# Analog.net
KiCad netlist of a schematic drawn in Altium Designer
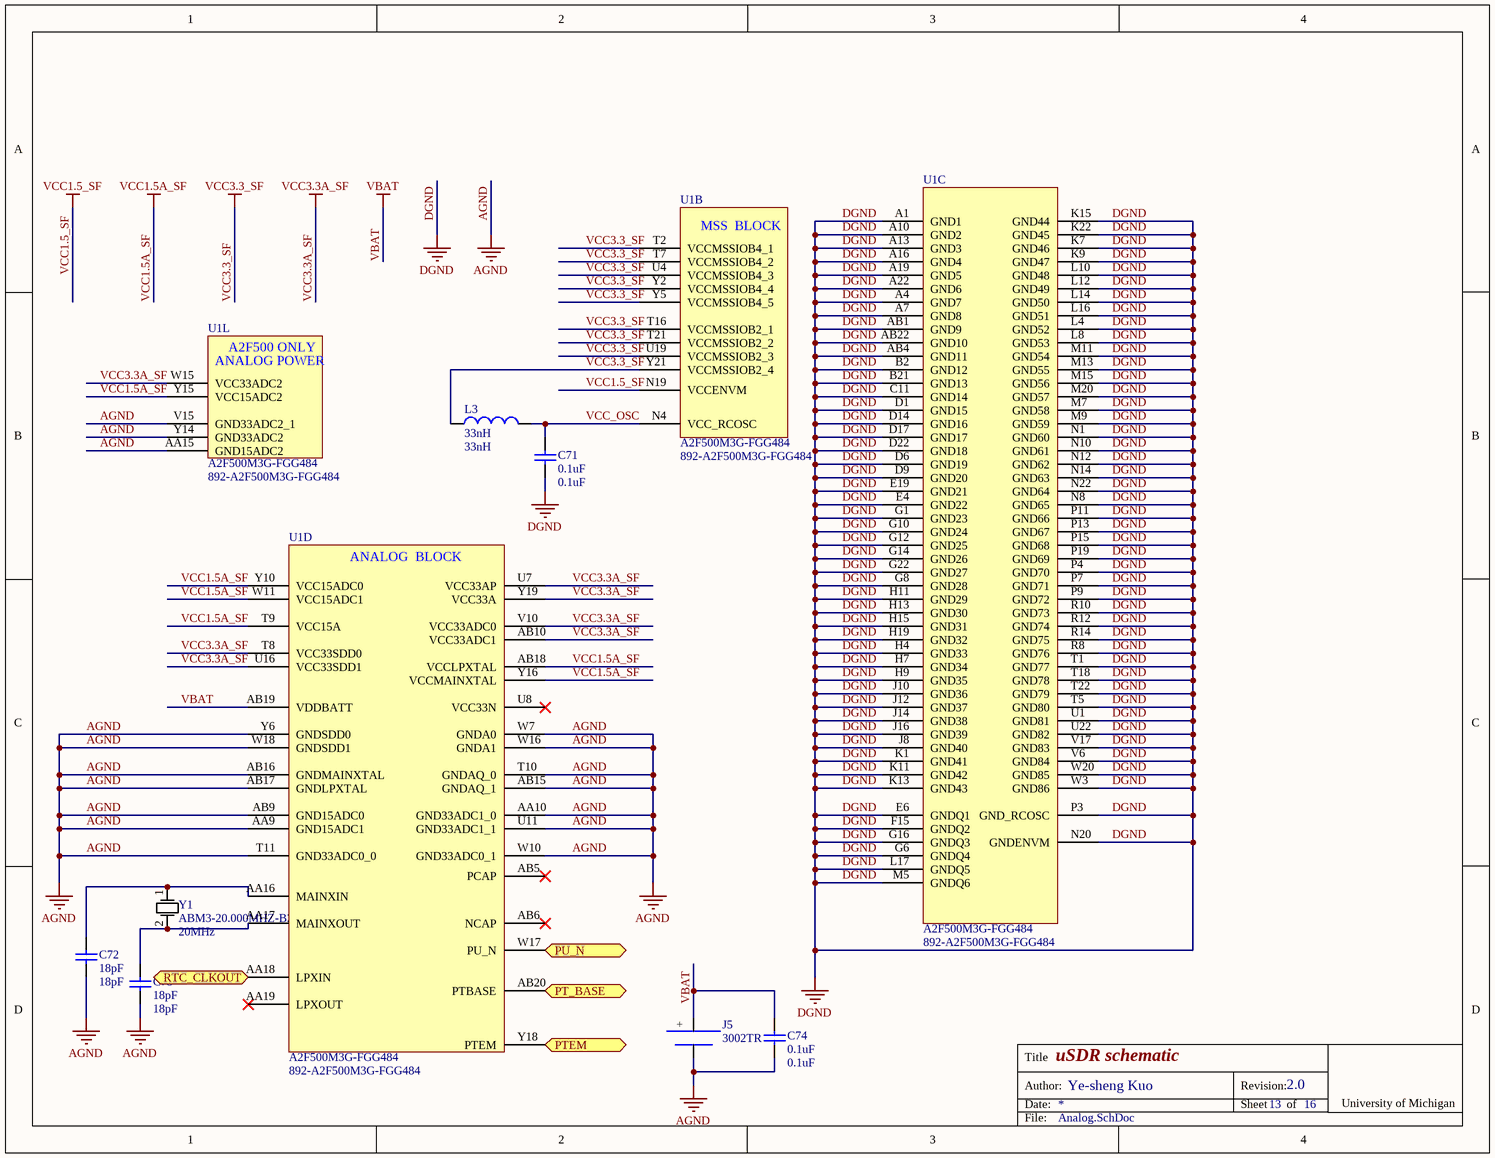
[diagram p0: Analog.SchDoc]

(export (version "E")
  (design (tool "Eeschema 10.0.6"))
  (components
    (comp (ref "C71")
      (value "0.1uF")
      (footprint "0402")
      (description "Capacitor (Semiconductor SIM Model)")
      (fields (field (name "ALTIUM_VALUE") "0.1uF") (field (name "PUBLISHER") "Altium Limited"))
      (libsource (lib "Miscellaneous Devices") (part "Cap Semi"))
    )
    (comp (ref "C72")
      (value "18pF")
      (footprint "0402")
      (description "Capacitor (Semiconductor SIM Model)")
      (fields (field (name "ALTIUM_VALUE") "18pF") (field (name "PUBLISHER") "Altium Limited"))
      (libsource (lib "Miscellaneous Devices") (part "Cap Semi"))
    )
    (comp (ref "C73")
      (value "18pF")
      (footprint "0402")
      (description "Capacitor (Semiconductor SIM Model)")
      (fields (field (name "ALTIUM_VALUE") "18pF") (field (name "PUBLISHER") "Altium Limited"))
      (libsource (lib "Miscellaneous Devices") (part "Cap Semi"))
    )
    (comp (ref "C74")
      (value "0.1uF")
      (footprint "0402")
      (description "Capacitor (Semiconductor SIM Model)")
      (fields (field (name "ALTIUM_VALUE") "0.1uF") (field (name "PUBLISHER") "Altium Limited"))
      (libsource (lib "Miscellaneous Devices") (part "Cap Semi"))
    )
    (comp (ref "J5")
      (value "3002TR")
      (footprint "3002TR")
      (description "HOLDER BATTERY COIN 20MM DIA SMD")
      (libsource (lib "SDR") (part "3002TR"))
    )
    (comp (ref "L3")
      (value "33nH")
      (footprint "0402")
      (description "Inductor")
      (fields (field (name "ALTIUM_VALUE") "33nH") (field (name "PUBLISHER") "Altium Limited"))
      (libsource (lib "Miscellaneous Devices") (part "Inductor"))
    )
    (comp (ref "U1")
      (value "A2F500M3G-FGG484")
      (footprint "BGA100P22X22-484N")
      (description "FPGA - Field Programmable Gate Array 500K System Gates")
      (fields (field (name "SUPPLIER PART NUMBER 1") "892-A2F500M3G-FGG484"))
      (libsource (lib "SDR") (part "F2-200_500-FGG484_1"))
    )
    (comp (ref "Y1")
      (value "ABM3-20.000MHZ-B2-T")
      (footprint "ABM3")
      (description "CRYSTAL 20.000MHZ 18PF SMD")
      (fields (field (name "ALTIUM_VALUE") "20MHz"))
      (libsource (lib "SDR") (part "ABM3"))
    )
  )
  (nets
    (net (code "1") (name "/PTEM") (class "Default")
      (node (ref "U1") (pin "Y18") (pinfunction "PTEM_Y18") (pintype "power_in"))
    )
    (net (code "2") (name "/PT_BASE") (class "Default")
      (node (ref "U1") (pin "AB20") (pinfunction "PTBASE_AB20") (pintype "power_in"))
    )
    (net (code "3") (name "/PU_N") (class "Default")
      (node (ref "U1") (pin "W17") (pinfunction "PU_N_W17") (pintype "power_in"))
    )
    (net (code "4") (name "/RTC_CLKOUT") (class "Default")
      (node (ref "U1") (pin "AA18") (pinfunction "LPXIN_AA18") (pintype "power_in"))
    )
    (net (code "5") (name "/VCC_OSC") (class "Default")
      (node (ref "C71") (pin "2") (pinfunction "2_2") (pintype "passive"))
      (node (ref "L3") (pin "2") (pinfunction "2_2") (pintype "passive"))
      (node (ref "U1") (pin "N4") (pinfunction "VCC_RCOSC_N4") (pintype "power_in"))
    )
    (net (code "6") (name "AGND") (class "Default")
      (node (ref "C72") (pin "1") (pinfunction "1_1") (pintype "passive"))
      (node (ref "C73") (pin "1") (pinfunction "1_1") (pintype "passive"))
      (node (ref "C74") (pin "1") (pinfunction "1_1") (pintype "passive"))
      (node (ref "J5") (pin "neg") (pinfunction "-_neg") (pintype "passive"))
      (node (ref "U1") (pin "AA10") (pinfunction "GND33ADC1_0_AA10") (pintype "power_in"))
      (node (ref "U1") (pin "AA15") (pinfunction "GND15ADC2_AA15") (pintype "power_in"))
      (node (ref "U1") (pin "AA9") (pinfunction "GND15ADC1_AA9") (pintype "power_in"))
      (node (ref "U1") (pin "AB15") (pinfunction "GNDAQ_1_AB15") (pintype "power_in"))
      (node (ref "U1") (pin "AB16") (pinfunction "GNDMAINXTAL_AB16") (pintype "power_in"))
      (node (ref "U1") (pin "AB17") (pinfunction "GNDLPXTAL_AB17") (pintype "power_in"))
      (node (ref "U1") (pin "AB9") (pinfunction "GND15ADC0_AB9") (pintype "power_in"))
      (node (ref "U1") (pin "T10") (pinfunction "GNDAQ_0_T10") (pintype "power_in"))
      (node (ref "U1") (pin "T11") (pinfunction "GND33ADC0_0_T11") (pintype "power_in"))
      (node (ref "U1") (pin "U11") (pinfunction "GND33ADC1_1_U11") (pintype "power_in"))
      (node (ref "U1") (pin "V15") (pinfunction "GND33ADC2_1_V15") (pintype "power_in"))
      (node (ref "U1") (pin "W10") (pinfunction "GND33ADC0_1_W10") (pintype "power_in"))
      (node (ref "U1") (pin "W16") (pinfunction "GNDA1_W16") (pintype "power_in"))
      (node (ref "U1") (pin "W18") (pinfunction "GNDSDD1_W18") (pintype "power_in"))
      (node (ref "U1") (pin "W7") (pinfunction "GNDA0_W7") (pintype "power_in"))
      (node (ref "U1") (pin "Y14") (pinfunction "GND33ADC2_Y14") (pintype "power_in"))
      (node (ref "U1") (pin "Y6") (pinfunction "GNDSDD0_Y6") (pintype "power_in"))
    )
    (net (code "7") (name "DGND") (class "Default")
      (node (ref "C71") (pin "1") (pinfunction "1_1") (pintype "passive"))
      (node (ref "U1") (pin "A1") (pinfunction "GND1_A1") (pintype "power_in"))
      (node (ref "U1") (pin "A10") (pinfunction "GND2_A10") (pintype "power_in"))
      (node (ref "U1") (pin "A13") (pinfunction "GND3_A13") (pintype "power_in"))
      (node (ref "U1") (pin "A16") (pinfunction "GND4_A16") (pintype "power_in"))
      (node (ref "U1") (pin "A19") (pinfunction "GND5_A19") (pintype "power_in"))
      (node (ref "U1") (pin "A22") (pinfunction "GND6_A22") (pintype "power_in"))
      (node (ref "U1") (pin "A4") (pinfunction "GND7_A4") (pintype "power_in"))
      (node (ref "U1") (pin "A7") (pinfunction "GND8_A7") (pintype "power_in"))
      (node (ref "U1") (pin "AB1") (pinfunction "GND9_AB1") (pintype "power_in"))
      (node (ref "U1") (pin "AB22") (pinfunction "GND10_AB22") (pintype "power_in"))
      (node (ref "U1") (pin "AB4") (pinfunction "GND11_AB4") (pintype "power_in"))
      (node (ref "U1") (pin "B2") (pinfunction "GND12_B2") (pintype "power_in"))
      (node (ref "U1") (pin "B21") (pinfunction "GND13_B21") (pintype "power_in"))
      (node (ref "U1") (pin "C11") (pinfunction "GND14_C11") (pintype "power_in"))
      (node (ref "U1") (pin "D1") (pinfunction "GND15_D1") (pintype "power_in"))
      (node (ref "U1") (pin "D14") (pinfunction "GND16_D14") (pintype "power_in"))
      (node (ref "U1") (pin "D17") (pinfunction "GND17_D17") (pintype "power_in"))
      (node (ref "U1") (pin "D22") (pinfunction "GND18_D22") (pintype "power_in"))
      (node (ref "U1") (pin "D6") (pinfunction "GND19_D6") (pintype "power_in"))
      (node (ref "U1") (pin "D9") (pinfunction "GND20_D9") (pintype "power_in"))
      (node (ref "U1") (pin "E19") (pinfunction "GND21_E19") (pintype "power_in"))
      (node (ref "U1") (pin "E4") (pinfunction "GND22_E4") (pintype "power_in"))
      (node (ref "U1") (pin "E6") (pinfunction "GNDQ1_E6") (pintype "power_in"))
      (node (ref "U1") (pin "F15") (pinfunction "GNDQ2_F15") (pintype "power_in"))
      (node (ref "U1") (pin "G1") (pinfunction "GND23_G1") (pintype "power_in"))
      (node (ref "U1") (pin "G10") (pinfunction "GND24_G10") (pintype "power_in"))
      (node (ref "U1") (pin "G12") (pinfunction "GND25_G12") (pintype "power_in"))
      (node (ref "U1") (pin "G14") (pinfunction "GND26_G14") (pintype "power_in"))
      (node (ref "U1") (pin "G16") (pinfunction "GNDQ3_G16") (pintype "power_in"))
      (node (ref "U1") (pin "G22") (pinfunction "GND27_G22") (pintype "power_in"))
      (node (ref "U1") (pin "G6") (pinfunction "GNDQ4_G6") (pintype "power_in"))
      (node (ref "U1") (pin "G8") (pinfunction "GND28_G8") (pintype "power_in"))
      (node (ref "U1") (pin "H11") (pinfunction "GND29_H11") (pintype "power_in"))
      (node (ref "U1") (pin "H13") (pinfunction "GND30_H13") (pintype "power_in"))
      (node (ref "U1") (pin "H15") (pinfunction "GND31_H15") (pintype "power_in"))
      (node (ref "U1") (pin "H19") (pinfunction "GND32_H19") (pintype "power_in"))
      (node (ref "U1") (pin "H4") (pinfunction "GND33_H4") (pintype "power_in"))
      (node (ref "U1") (pin "H7") (pinfunction "GND34_H7") (pintype "power_in"))
      (node (ref "U1") (pin "H9") (pinfunction "GND35_H9") (pintype "power_in"))
      (node (ref "U1") (pin "J10") (pinfunction "GND36_J10") (pintype "power_in"))
      (node (ref "U1") (pin "J12") (pinfunction "GND37_J12") (pintype "power_in"))
      (node (ref "U1") (pin "J14") (pinfunction "GND38_J14") (pintype "power_in"))
      (node (ref "U1") (pin "J16") (pinfunction "GND39_J16") (pintype "power_in"))
      (node (ref "U1") (pin "J8") (pinfunction "GND40_J8") (pintype "power_in"))
      (node (ref "U1") (pin "K1") (pinfunction "GND41_K1") (pintype "power_in"))
      (node (ref "U1") (pin "K11") (pinfunction "GND42_K11") (pintype "power_in"))
      (node (ref "U1") (pin "K13") (pinfunction "GND43_K13") (pintype "power_in"))
      (node (ref "U1") (pin "K15") (pinfunction "GND44_K15") (pintype "power_in"))
      (node (ref "U1") (pin "K22") (pinfunction "GND45_K22") (pintype "power_in"))
      (node (ref "U1") (pin "K7") (pinfunction "GND46_K7") (pintype "power_in"))
      (node (ref "U1") (pin "K9") (pinfunction "GND47_K9") (pintype "power_in"))
      (node (ref "U1") (pin "L10") (pinfunction "GND48_L10") (pintype "power_in"))
      (node (ref "U1") (pin "L12") (pinfunction "GND49_L12") (pintype "power_in"))
      (node (ref "U1") (pin "L14") (pinfunction "GND50_L14") (pintype "power_in"))
      (node (ref "U1") (pin "L16") (pinfunction "GND51_L16") (pintype "power_in"))
      (node (ref "U1") (pin "L17") (pinfunction "GNDQ5_L17") (pintype "power_in"))
      (node (ref "U1") (pin "L4") (pinfunction "GND52_L4") (pintype "power_in"))
      (node (ref "U1") (pin "L8") (pinfunction "GND53_L8") (pintype "power_in"))
      (node (ref "U1") (pin "M11") (pinfunction "GND54_M11") (pintype "power_in"))
      (node (ref "U1") (pin "M13") (pinfunction "GND55_M13") (pintype "power_in"))
      (node (ref "U1") (pin "M15") (pinfunction "GND56_M15") (pintype "power_in"))
      (node (ref "U1") (pin "M20") (pinfunction "GND57_M20") (pintype "power_in"))
      (node (ref "U1") (pin "M5") (pinfunction "GNDQ6_M5") (pintype "power_in"))
      (node (ref "U1") (pin "M7") (pinfunction "GND58_M7") (pintype "power_in"))
      (node (ref "U1") (pin "M9") (pinfunction "GND59_M9") (pintype "power_in"))
      (node (ref "U1") (pin "N1") (pinfunction "GND60_N1") (pintype "power_in"))
      (node (ref "U1") (pin "N10") (pinfunction "GND61_N10") (pintype "power_in"))
      (node (ref "U1") (pin "N12") (pinfunction "GND62_N12") (pintype "power_in"))
      (node (ref "U1") (pin "N14") (pinfunction "GND63_N14") (pintype "power_in"))
      (node (ref "U1") (pin "N20") (pinfunction "GNDENVM_N20") (pintype "power_in"))
      (node (ref "U1") (pin "N22") (pinfunction "GND64_N22") (pintype "power_in"))
      (node (ref "U1") (pin "N8") (pinfunction "GND65_N8") (pintype "power_in"))
      (node (ref "U1") (pin "P11") (pinfunction "GND66_P11") (pintype "power_in"))
      (node (ref "U1") (pin "P13") (pinfunction "GND67_P13") (pintype "power_in"))
      (node (ref "U1") (pin "P15") (pinfunction "GND68_P15") (pintype "power_in"))
      (node (ref "U1") (pin "P19") (pinfunction "GND69_P19") (pintype "power_in"))
      (node (ref "U1") (pin "P3") (pinfunction "GND_RCOSC_P3") (pintype "power_in"))
      (node (ref "U1") (pin "P4") (pinfunction "GND70_P4") (pintype "power_in"))
      (node (ref "U1") (pin "P7") (pinfunction "GND71_P7") (pintype "power_in"))
      (node (ref "U1") (pin "P9") (pinfunction "GND72_P9") (pintype "power_in"))
      (node (ref "U1") (pin "R10") (pinfunction "GND73_R10") (pintype "power_in"))
      (node (ref "U1") (pin "R12") (pinfunction "GND74_R12") (pintype "power_in"))
      (node (ref "U1") (pin "R14") (pinfunction "GND75_R14") (pintype "power_in"))
      (node (ref "U1") (pin "R8") (pinfunction "GND76_R8") (pintype "power_in"))
      (node (ref "U1") (pin "T1") (pinfunction "GND77_T1") (pintype "power_in"))
      (node (ref "U1") (pin "T18") (pinfunction "GND78_T18") (pintype "power_in"))
      (node (ref "U1") (pin "T22") (pinfunction "GND79_T22") (pintype "power_in"))
      (node (ref "U1") (pin "T5") (pinfunction "GND80_T5") (pintype "power_in"))
      (node (ref "U1") (pin "U1") (pinfunction "GND81_U1") (pintype "power_in"))
      (node (ref "U1") (pin "U22") (pinfunction "GND82_U22") (pintype "power_in"))
      (node (ref "U1") (pin "V17") (pinfunction "GND83_V17") (pintype "power_in"))
      (node (ref "U1") (pin "V6") (pinfunction "GND84_V6") (pintype "power_in"))
      (node (ref "U1") (pin "W20") (pinfunction "GND85_W20") (pintype "power_in"))
      (node (ref "U1") (pin "W3") (pinfunction "GND86_W3") (pintype "power_in"))
    )
    (net (code "8") (name "Net-(U1D-MAINXIN)") (class "Default")
      (node (ref "C72") (pin "2") (pinfunction "2_2") (pintype "passive"))
      (node (ref "U1") (pin "AA16") (pinfunction "MAINXIN_AA16") (pintype "power_in"))
      (node (ref "Y1") (pin "1") (pinfunction "HOT_1") (pintype "passive"))
    )
    (net (code "9") (name "Net-(U1D-MAINXOUT)") (class "Default")
      (node (ref "C73") (pin "2") (pinfunction "2_2") (pintype "passive"))
      (node (ref "U1") (pin "AA17") (pinfunction "MAINXOUT_AA17") (pintype "power_in"))
      (node (ref "Y1") (pin "2") (pinfunction "HOT_2") (pintype "passive"))
    )
    (net (code "10") (name "VBAT") (class "Default")
      (node (ref "C74") (pin "2") (pinfunction "2_2") (pintype "passive"))
      (node (ref "J5") (pin "pos") (pinfunction "+_pos") (pintype "passive"))
      (node (ref "U1") (pin "AB19") (pinfunction "VDDBATT_AB19") (pintype "power_in"))
    )
    (net (code "11") (name "VCC1.5A_SF") (class "Default")
      (node (ref "U1") (pin "AB18") (pinfunction "VCCLPXTAL_AB18") (pintype "power_in"))
      (node (ref "U1") (pin "T9") (pinfunction "VCC15A_T9") (pintype "power_in"))
      (node (ref "U1") (pin "W11") (pinfunction "VCC15ADC1_W11") (pintype "power_in"))
      (node (ref "U1") (pin "Y10") (pinfunction "VCC15ADC0_Y10") (pintype "power_in"))
      (node (ref "U1") (pin "Y15") (pinfunction "VCC15ADC2_Y15") (pintype "power_in"))
      (node (ref "U1") (pin "Y16") (pinfunction "VCCMAINXTAL_Y16") (pintype "power_in"))
    )
    (net (code "12") (name "VCC1.5_SF") (class "Default")
      (node (ref "U1") (pin "N19") (pinfunction "VCCENVM_N19") (pintype "power_in"))
    )
    (net (code "13") (name "VCC3.3A_SF") (class "Default")
      (node (ref "U1") (pin "AB10") (pinfunction "VCC33ADC1_AB10") (pintype "power_in"))
      (node (ref "U1") (pin "T8") (pinfunction "VCC33SDD0_T8") (pintype "power_in"))
      (node (ref "U1") (pin "U16") (pinfunction "VCC33SDD1_U16") (pintype "power_in"))
      (node (ref "U1") (pin "U7") (pinfunction "VCC33AP_U7") (pintype "power_in"))
      (node (ref "U1") (pin "V10") (pinfunction "VCC33ADC0_V10") (pintype "power_in"))
      (node (ref "U1") (pin "W15") (pinfunction "VCC33ADC2_W15") (pintype "power_in"))
      (node (ref "U1") (pin "Y19") (pinfunction "VCC33A_Y19") (pintype "power_in"))
    )
    (net (code "14") (name "VCC3.3_SF") (class "Default")
      (node (ref "L3") (pin "1") (pinfunction "1_1") (pintype "passive"))
      (node (ref "U1") (pin "T16") (pinfunction "VCCMSSIOB2_1_T16") (pintype "power_in"))
      (node (ref "U1") (pin "T2") (pinfunction "VCCMSSIOB4_1_T2") (pintype "power_in"))
      (node (ref "U1") (pin "T21") (pinfunction "VCCMSSIOB2_2_T21") (pintype "power_in"))
      (node (ref "U1") (pin "T7") (pinfunction "VCCMSSIOB4_2_T7") (pintype "power_in"))
      (node (ref "U1") (pin "U19") (pinfunction "VCCMSSIOB2_3_U19") (pintype "power_in"))
      (node (ref "U1") (pin "U4") (pinfunction "VCCMSSIOB4_3_U4") (pintype "power_in"))
      (node (ref "U1") (pin "Y2") (pinfunction "VCCMSSIOB4_4_Y2") (pintype "power_in"))
      (node (ref "U1") (pin "Y21") (pinfunction "VCCMSSIOB2_4_Y21") (pintype "power_in"))
      (node (ref "U1") (pin "Y5") (pinfunction "VCCMSSIOB4_5_Y5") (pintype "power_in"))
    )
    (net (code "15") (name "unconnected-(U1D-LPXOUT-PadAA19)") (class "Default")
      (node (ref "U1") (pin "AA19") (pinfunction "LPXOUT_AA19") (pintype "power_in+no_connect"))
    )
    (net (code "16") (name "unconnected-(U1D-NCAP-PadAB6)") (class "Default")
      (node (ref "U1") (pin "AB6") (pinfunction "NCAP_AB6") (pintype "power_in+no_connect"))
    )
    (net (code "17") (name "unconnected-(U1D-PCAP-PadAB5)") (class "Default")
      (node (ref "U1") (pin "AB5") (pinfunction "PCAP_AB5") (pintype "power_in+no_connect"))
    )
    (net (code "18") (name "unconnected-(U1D-VCC33N-PadU8)") (class "Default")
      (node (ref "U1") (pin "U8") (pinfunction "VCC33N_U8") (pintype "power_in+no_connect"))
    )
  )
)
